# Pulsar_Buddy_rev_A.net
KiCad netlist of a schematic drawn in EAGLE
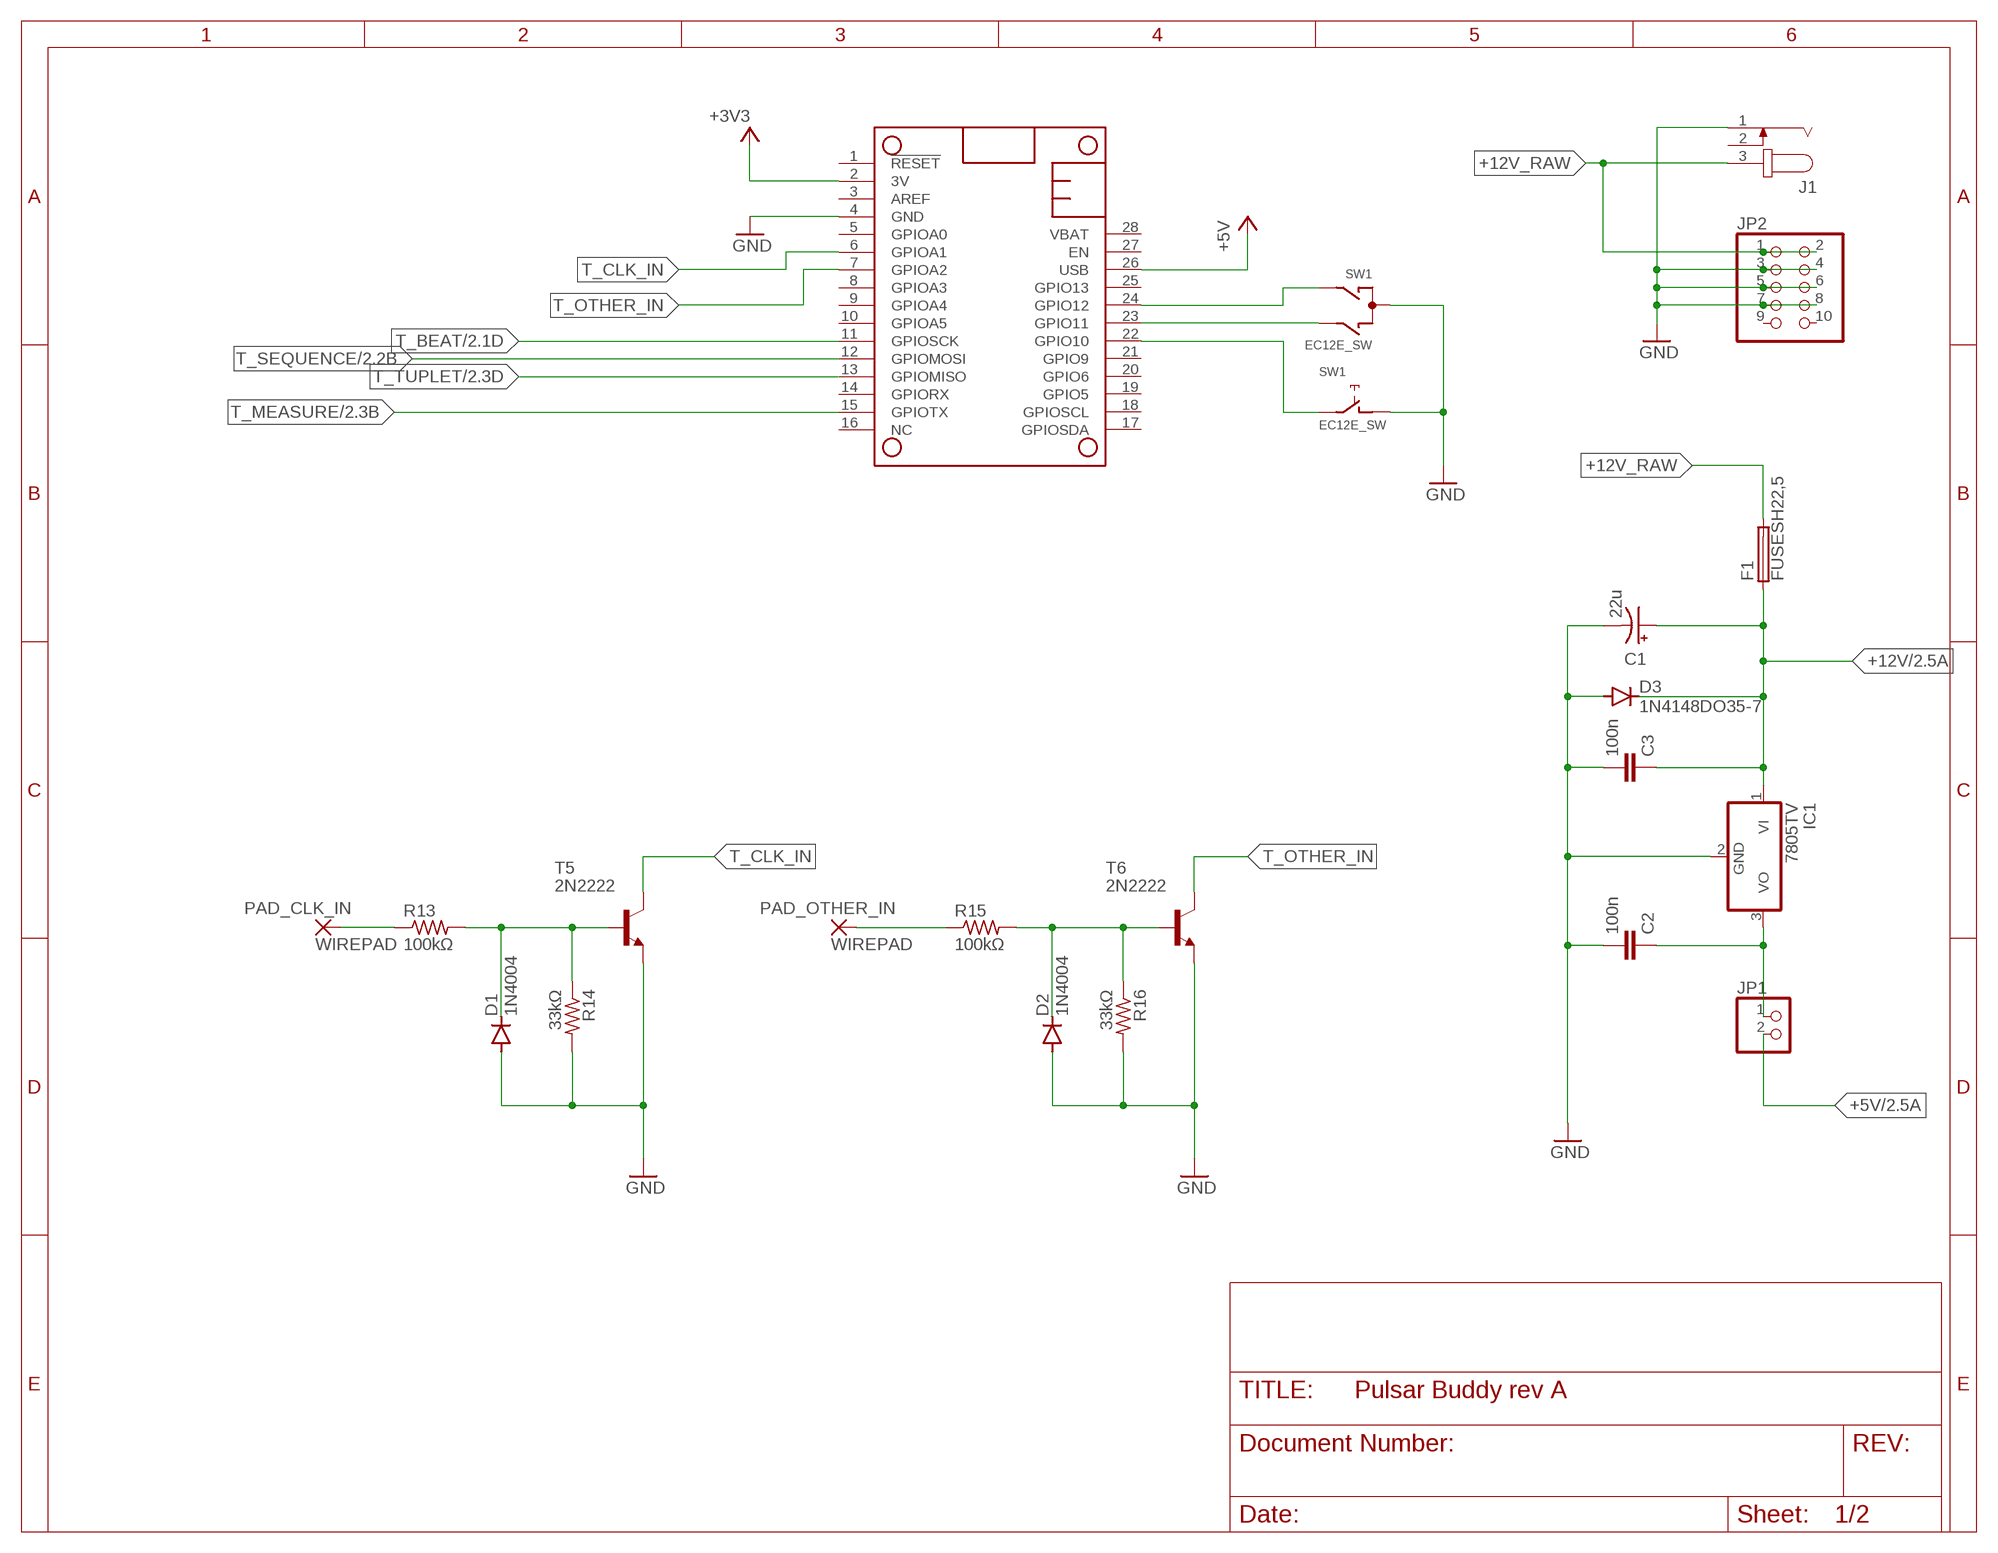
[diagram p0: schematic, sheet 1]
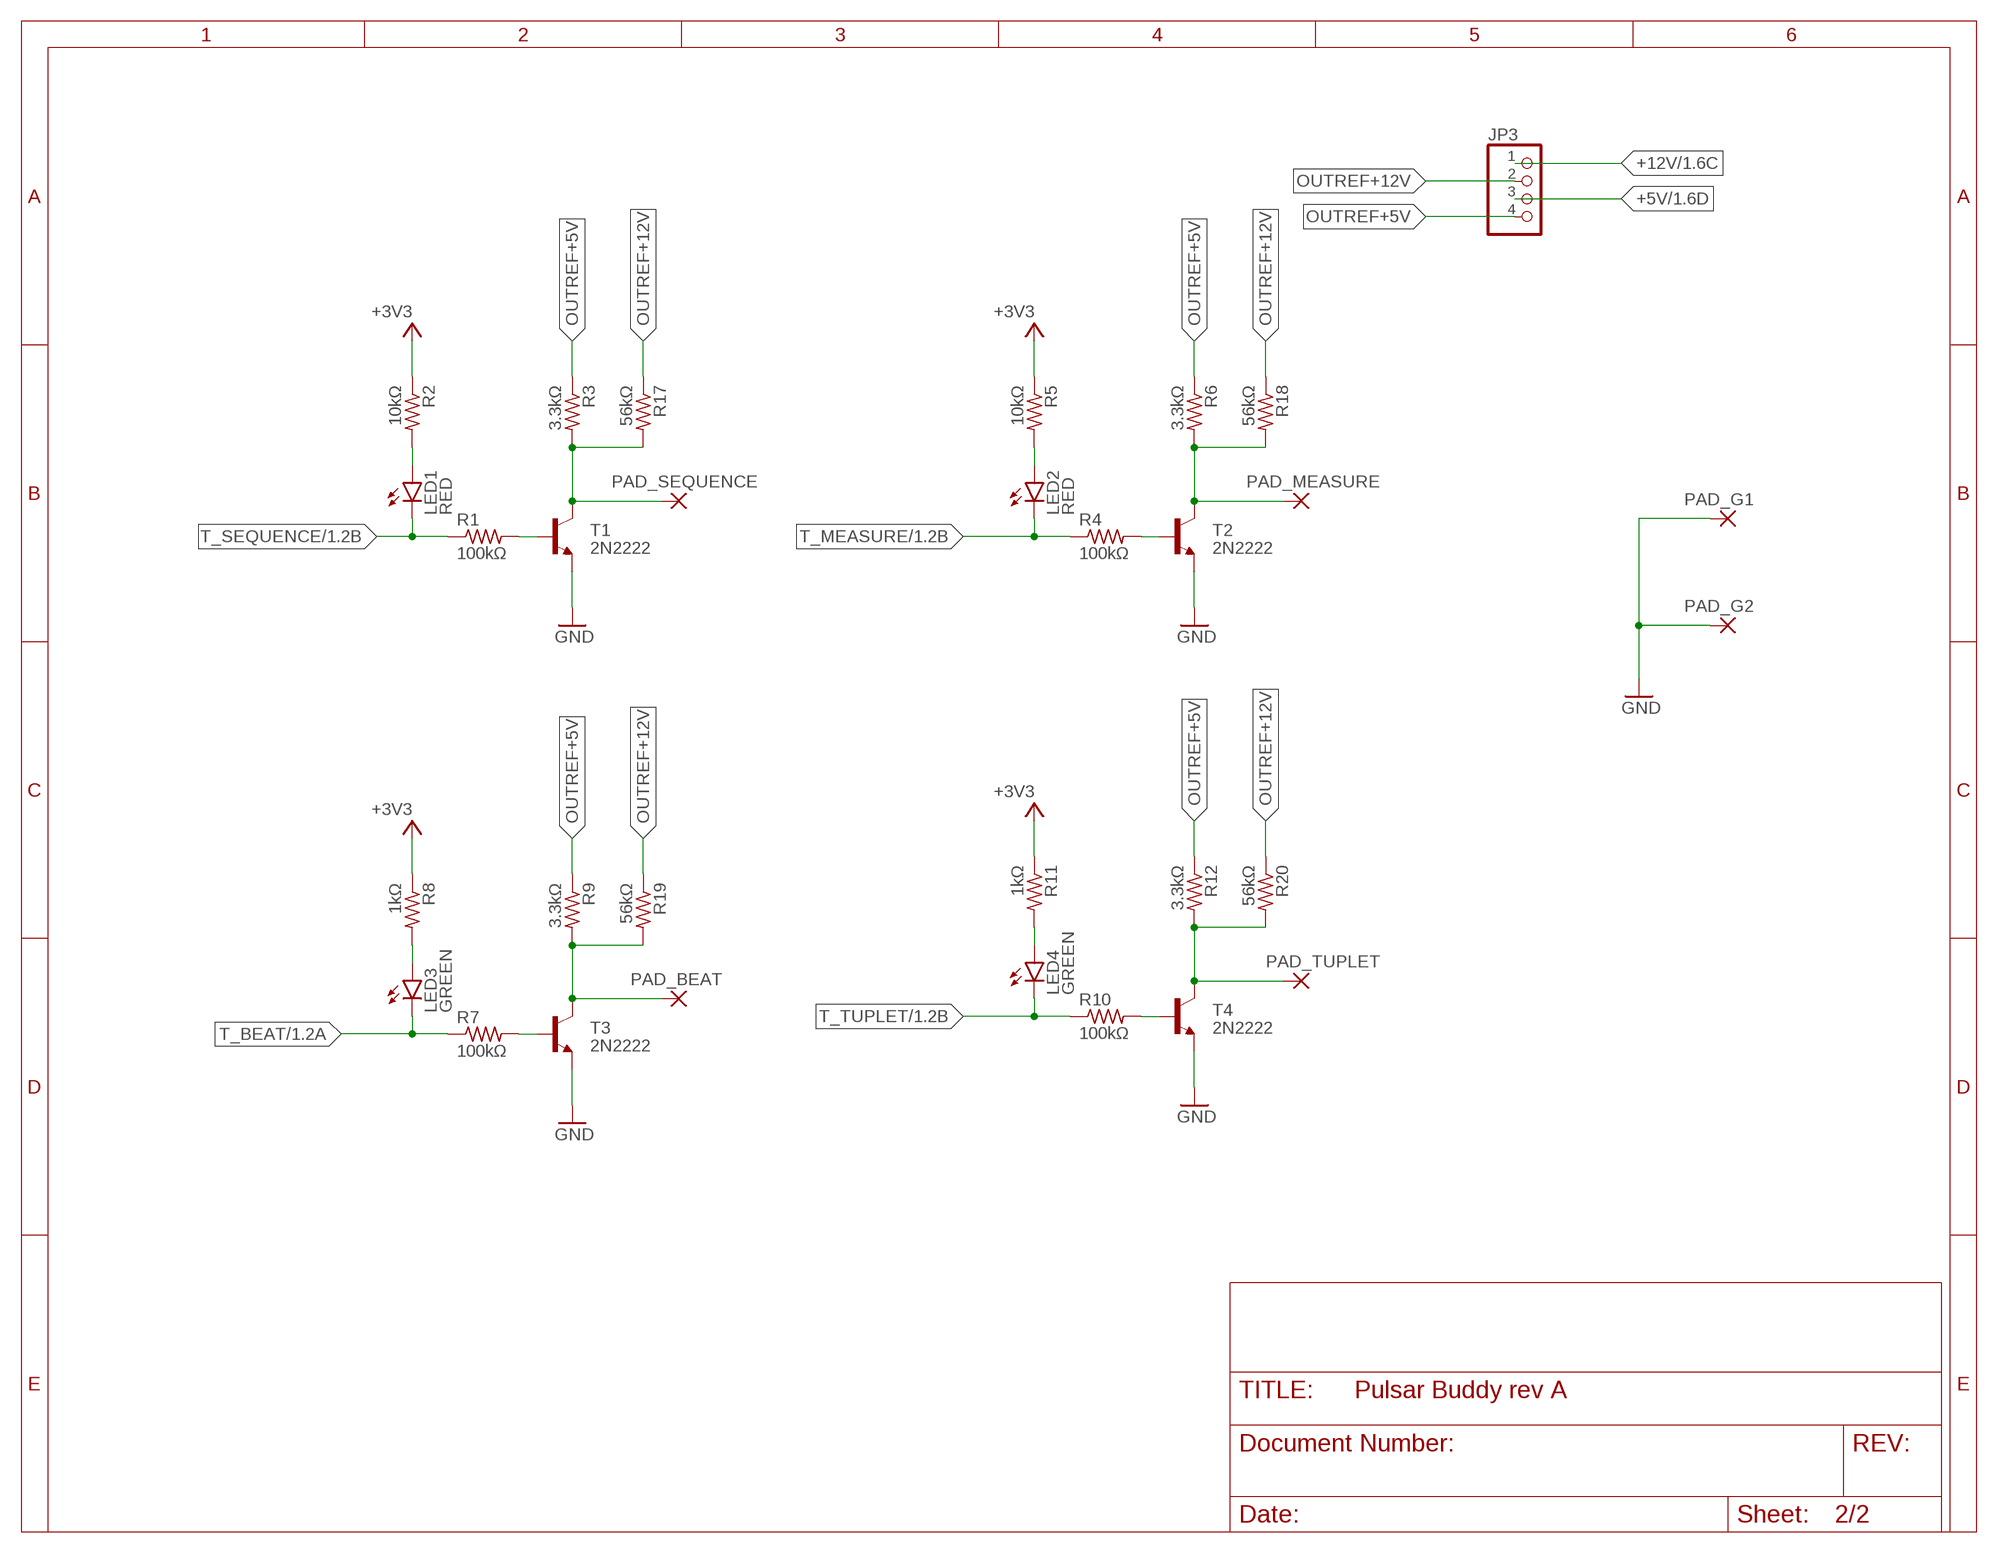
[diagram p1: schematic, sheet 2]

(export (version "E")
  (design (tool "Eeschema 10.0.6"))
  (components
    (comp (ref "C1")
      (value "22u")
      (footprint "eagle-import:E3,5-8")
      (libsource (lib "eagle-import") (part "CPOL-USE3.5-8"))
    )
    (comp (ref "C2")
      (value "100n")
      (footprint "eagle-import:C025-024X044")
      (libsource (lib "eagle-import") (part "C-EU025-024X044"))
    )
    (comp (ref "C3")
      (value "100n")
      (footprint "eagle-import:C025-024X044")
      (libsource (lib "eagle-import") (part "C-EU025-024X044"))
    )
    (comp (ref "D1")
      (value "1N4004")
      (footprint "eagle-import:DO41-10")
      (libsource (lib "eagle-import") (part "1N4004"))
    )
    (comp (ref "D2")
      (value "1N4004")
      (footprint "eagle-import:DO41-10")
      (libsource (lib "eagle-import") (part "1N4004"))
    )
    (comp (ref "D3")
      (value "1N4148DO35-7")
      (footprint "eagle-import:DO35-7")
      (libsource (lib "eagle-import") (part "1N4148DO35-7"))
    )
    (comp (ref "F1")
      (value "FUSESH22,5")
      (footprint "eagle-import:SH22,5")
      (libsource (lib "eagle-import") (part "FUSESH22,5"))
    )
    (comp (ref "IC1")
      (value "7805TV")
      (footprint "eagle-import:TO220V")
      (libsource (lib "eagle-import") (part "78TV05"))
    )
    (comp (ref "J1")
      (value "JACK-PLUG0")
      (footprint "eagle-import:SPC4077")
      (libsource (lib "eagle-import") (part "JACK-PLUG0"))
    )
    (comp (ref "JP1")
      (value "PINHD-1X2")
      (footprint "eagle-import:1X02")
      (libsource (lib "eagle-import") (part "PINHD-1X2"))
    )
    (comp (ref "JP2")
      (value "PINHD-2X5")
      (footprint "eagle-import:2X05")
      (libsource (lib "eagle-import") (part "PINHD-2X5"))
    )
    (comp (ref "MS2")
      (value "FEATHERWING_NODIM")
      (footprint "eagle-import:FEATHERWING_DIM")
      (libsource (lib "eagle-import") (part "FEATHERWING_NODIM"))
    )
    (comp (ref "PAD_CLK_IN")
      (value "WIREPAD")
      (footprint "eagle-import:M3")
      (libsource (lib "eagle-import") (part "WIREPAD"))
    )
    (comp (ref "PAD_OTHER_IN")
      (value "WIREPAD")
      (footprint "eagle-import:M3")
      (libsource (lib "eagle-import") (part "WIREPAD"))
    )
    (comp (ref "R13")
      (value "100kΩ")
      (footprint "eagle-import:0204_7")
      (libsource (lib "eagle-import") (part "R-US_0204/7"))
    )
    (comp (ref "R14")
      (value "33kΩ")
      (footprint "eagle-import:0204_7")
      (libsource (lib "eagle-import") (part "R-US_0204/7"))
    )
    (comp (ref "R15")
      (value "100kΩ")
      (footprint "eagle-import:0204_7")
      (libsource (lib "eagle-import") (part "R-US_0204/7"))
    )
    (comp (ref "R16")
      (value "33kΩ")
      (footprint "eagle-import:0204_7")
      (libsource (lib "eagle-import") (part "R-US_0204/7"))
    )
    (comp (ref "SW1")
      (value "EC12E_SW")
      (footprint "eagle-import:ALPS_EC12E_SW")
      (fields (field (name "MPN") "EC12E2424407"))
      (libsource (lib "eagle-import") (part "EC12E_SW"))
    )
    (comp (ref "T5")
      (value "2N2222")
      (footprint "eagle-import:TO92-EBC-OVAL")
      (libsource (lib "eagle-import") (part "2N2222"))
    )
    (comp (ref "T6")
      (value "2N2222")
      (footprint "eagle-import:TO92-EBC-OVAL")
      (libsource (lib "eagle-import") (part "2N2222"))
    )
    (comp (ref "JP3")
      (value "PINHD-1X4")
      (footprint "eagle-import:1X04")
      (libsource (lib "eagle-import") (part "PINHD-1X4"))
    )
    (comp (ref "LED1")
      (value "RED")
      (footprint "eagle-import:LED5MM")
      (libsource (lib "eagle-import") (part "LED5MM"))
    )
    (comp (ref "LED2")
      (value "RED")
      (footprint "eagle-import:LED5MM")
      (libsource (lib "eagle-import") (part "LED5MM"))
    )
    (comp (ref "LED3")
      (value "GREEN")
      (footprint "eagle-import:LED5MM")
      (libsource (lib "eagle-import") (part "LED5MM"))
    )
    (comp (ref "LED4")
      (value "GREEN")
      (footprint "eagle-import:LED5MM")
      (libsource (lib "eagle-import") (part "LED5MM"))
    )
    (comp (ref "PAD_BEAT")
      (value "WIREPAD")
      (footprint "eagle-import:M3")
      (libsource (lib "eagle-import") (part "WIREPAD"))
    )
    (comp (ref "PAD_G1")
      (value "WIREPAD")
      (footprint "eagle-import:M3")
      (libsource (lib "eagle-import") (part "WIREPAD"))
    )
    (comp (ref "PAD_G2")
      (value "WIREPAD")
      (footprint "eagle-import:M3")
      (libsource (lib "eagle-import") (part "WIREPAD"))
    )
    (comp (ref "PAD_MEASURE")
      (value "WIREPAD")
      (footprint "eagle-import:M3")
      (libsource (lib "eagle-import") (part "WIREPAD"))
    )
    (comp (ref "PAD_SEQUENCE")
      (value "WIREPAD")
      (footprint "eagle-import:M3")
      (libsource (lib "eagle-import") (part "WIREPAD"))
    )
    (comp (ref "PAD_TUPLET")
      (value "WIREPAD")
      (footprint "eagle-import:M3")
      (libsource (lib "eagle-import") (part "WIREPAD"))
    )
    (comp (ref "R1")
      (value "100kΩ")
      (footprint "eagle-import:0204_7")
      (libsource (lib "eagle-import") (part "R-US_0204/7"))
    )
    (comp (ref "R2")
      (value "10kΩ")
      (footprint "eagle-import:0204_7")
      (libsource (lib "eagle-import") (part "R-US_0204/7"))
    )
    (comp (ref "R3")
      (value "3.3kΩ")
      (footprint "eagle-import:0204_7")
      (libsource (lib "eagle-import") (part "R-US_0204/7"))
    )
    (comp (ref "R4")
      (value "100kΩ")
      (footprint "eagle-import:0204_7")
      (libsource (lib "eagle-import") (part "R-US_0204/7"))
    )
    (comp (ref "R5")
      (value "10kΩ")
      (footprint "eagle-import:0204_7")
      (libsource (lib "eagle-import") (part "R-US_0204/7"))
    )
    (comp (ref "R6")
      (value "3.3kΩ")
      (footprint "eagle-import:0204_7")
      (libsource (lib "eagle-import") (part "R-US_0204/7"))
    )
    (comp (ref "R7")
      (value "100kΩ")
      (footprint "eagle-import:0204_7")
      (libsource (lib "eagle-import") (part "R-US_0204/7"))
    )
    (comp (ref "R8")
      (value "1kΩ")
      (footprint "eagle-import:0204_7")
      (libsource (lib "eagle-import") (part "R-US_0204/7"))
    )
    (comp (ref "R9")
      (value "3.3kΩ")
      (footprint "eagle-import:0204_7")
      (libsource (lib "eagle-import") (part "R-US_0204/7"))
    )
    (comp (ref "R10")
      (value "100kΩ")
      (footprint "eagle-import:0204_7")
      (libsource (lib "eagle-import") (part "R-US_0204/7"))
    )
    (comp (ref "R11")
      (value "1kΩ")
      (footprint "eagle-import:0204_7")
      (libsource (lib "eagle-import") (part "R-US_0204/7"))
    )
    (comp (ref "R12")
      (value "3.3kΩ")
      (footprint "eagle-import:0204_7")
      (libsource (lib "eagle-import") (part "R-US_0204/7"))
    )
    (comp (ref "R17")
      (value "56kΩ")
      (footprint "eagle-import:0204_7")
      (libsource (lib "eagle-import") (part "R-US_0204/7"))
    )
    (comp (ref "R18")
      (value "56kΩ")
      (footprint "eagle-import:0204_7")
      (libsource (lib "eagle-import") (part "R-US_0204/7"))
    )
    (comp (ref "R19")
      (value "56kΩ")
      (footprint "eagle-import:0204_7")
      (libsource (lib "eagle-import") (part "R-US_0204/7"))
    )
    (comp (ref "R20")
      (value "56kΩ")
      (footprint "eagle-import:0204_7")
      (libsource (lib "eagle-import") (part "R-US_0204/7"))
    )
    (comp (ref "T1")
      (value "2N2222")
      (footprint "eagle-import:TO92-EBC-OVAL")
      (libsource (lib "eagle-import") (part "2N2222"))
    )
    (comp (ref "T2")
      (value "2N2222")
      (footprint "eagle-import:TO92-EBC-OVAL")
      (libsource (lib "eagle-import") (part "2N2222"))
    )
    (comp (ref "T3")
      (value "2N2222")
      (footprint "eagle-import:TO92-EBC-OVAL")
      (libsource (lib "eagle-import") (part "2N2222"))
    )
    (comp (ref "T4")
      (value "2N2222")
      (footprint "eagle-import:TO92-EBC-OVAL")
      (libsource (lib "eagle-import") (part "2N2222"))
    )
  )
  (nets
    (net (code "1") (name "+3V3") (class "Default")
      (node (ref "MS2") (pin "2") (pinfunction "3V_2") (pintype "power_in"))
      (node (ref "R11") (pin "1") (pinfunction "1_1") (pintype "passive"))
      (node (ref "R2") (pin "1") (pinfunction "1_1") (pintype "passive"))
      (node (ref "R5") (pin "1") (pinfunction "1_1") (pintype "passive"))
      (node (ref "R8") (pin "1") (pinfunction "1_1") (pintype "passive"))
    )
    (net (code "2") (name "+5V") (class "Default")
      (node (ref "JP1") (pin "2") (pinfunction "2_2") (pintype "passive"))
      (node (ref "JP3") (pin "3") (pinfunction "3_3") (pintype "passive"))
      (node (ref "MS2") (pin "26") (pinfunction "USB_26") (pintype "power_in"))
    )
    (net (code "3") (name "+12V") (class "Default")
      (node (ref "C1") (pin "+") (pinfunction "+_+") (pintype "passive"))
      (node (ref "C3") (pin "1") (pinfunction "1_1") (pintype "passive"))
      (node (ref "D3") (pin "C") (pinfunction "C_C") (pintype "passive"))
      (node (ref "F1") (pin "1") (pinfunction "1_1") (pintype "passive"))
      (node (ref "IC1") (pin "1") (pinfunction "VI_1") (pintype "input"))
      (node (ref "JP3") (pin "1") (pinfunction "1_1") (pintype "passive"))
    )
    (net (code "4") (name "+12V_RAW") (class "Default")
      (node (ref "F1") (pin "2") (pinfunction "2_2") (pintype "passive"))
      (node (ref "J1") (pin "3") (pinfunction "3_3") (pintype "passive"))
      (node (ref "JP2") (pin "1") (pinfunction "1_1") (pintype "passive"))
      (node (ref "JP2") (pin "2") (pinfunction "2_2") (pintype "passive"))
    )
    (net (code "5") (name "GND") (class "Default")
      (node (ref "C1") (pin "-") (pinfunction "-_-") (pintype "passive"))
      (node (ref "C2") (pin "2") (pinfunction "2_2") (pintype "passive"))
      (node (ref "C3") (pin "2") (pinfunction "2_2") (pintype "passive"))
      (node (ref "D1") (pin "A") (pinfunction "A_A") (pintype "passive"))
      (node (ref "D2") (pin "A") (pinfunction "A_A") (pintype "passive"))
      (node (ref "D3") (pin "A") (pinfunction "A_A") (pintype "passive"))
      (node (ref "IC1") (pin "2") (pinfunction "GND_2") (pintype "passive"))
      (node (ref "J1") (pin "1") (pinfunction "1_1") (pintype "passive"))
      (node (ref "JP2") (pin "3") (pinfunction "3_3") (pintype "passive"))
      (node (ref "JP2") (pin "4") (pinfunction "4_4") (pintype "passive"))
      (node (ref "JP2") (pin "5") (pinfunction "5_5") (pintype "passive"))
      (node (ref "JP2") (pin "6") (pinfunction "6_6") (pintype "passive"))
      (node (ref "JP2") (pin "7") (pinfunction "7_7") (pintype "passive"))
      (node (ref "JP2") (pin "8") (pinfunction "8_8") (pintype "passive"))
      (node (ref "MS2") (pin "4") (pinfunction "GND_4") (pintype "power_in"))
      (node (ref "PAD_G1") (pin "1") (pinfunction "P_1") (pintype "passive"))
      (node (ref "PAD_G2") (pin "1") (pinfunction "P_1") (pintype "passive"))
      (node (ref "R14") (pin "2") (pinfunction "2_2") (pintype "passive"))
      (node (ref "R16") (pin "2") (pinfunction "2_2") (pintype "passive"))
      (node (ref "SW1") (pin "C") (pinfunction "C_C") (pintype "passive"))
      (node (ref "SW1") (pin "D") (pinfunction "1_D") (pintype "passive"))
      (node (ref "T1") (pin "E") (pinfunction "E_E") (pintype "passive"))
      (node (ref "T2") (pin "E") (pinfunction "E_E") (pintype "passive"))
      (node (ref "T3") (pin "E") (pinfunction "E_E") (pintype "passive"))
      (node (ref "T4") (pin "E") (pinfunction "E_E") (pintype "passive"))
      (node (ref "T5") (pin "E") (pinfunction "E_E") (pintype "passive"))
      (node (ref "T6") (pin "E") (pinfunction "E_E") (pintype "passive"))
    )
    (net (code "6") (name "Net-(D1-PadC)") (class "Default")
      (node (ref "D1") (pin "C") (pinfunction "C_C") (pintype "passive"))
      (node (ref "R13") (pin "2") (pinfunction "2_2") (pintype "passive"))
      (node (ref "R14") (pin "1") (pinfunction "1_1") (pintype "passive"))
      (node (ref "T5") (pin "B") (pinfunction "B_B") (pintype "passive"))
    )
    (net (code "7") (name "Net-(D2-PadC)") (class "Default")
      (node (ref "D2") (pin "C") (pinfunction "C_C") (pintype "passive"))
      (node (ref "R15") (pin "2") (pinfunction "2_2") (pintype "passive"))
      (node (ref "R16") (pin "1") (pinfunction "1_1") (pintype "passive"))
      (node (ref "T6") (pin "B") (pinfunction "B_B") (pintype "passive"))
    )
    (net (code "8") (name "Net-(IC1-VO)") (class "Default")
      (node (ref "C2") (pin "1") (pinfunction "1_1") (pintype "passive"))
      (node (ref "IC1") (pin "3") (pinfunction "VO_3") (pintype "passive"))
      (node (ref "JP1") (pin "1") (pinfunction "1_1") (pintype "passive"))
    )
    (net (code "9") (name "Net-(LED1-PadA)") (class "Default")
      (node (ref "LED1") (pin "A") (pinfunction "A_A") (pintype "passive"))
      (node (ref "R2") (pin "2") (pinfunction "2_2") (pintype "passive"))
    )
    (net (code "10") (name "Net-(LED2-PadA)") (class "Default")
      (node (ref "LED2") (pin "A") (pinfunction "A_A") (pintype "passive"))
      (node (ref "R5") (pin "2") (pinfunction "2_2") (pintype "passive"))
    )
    (net (code "11") (name "Net-(LED3-PadA)") (class "Default")
      (node (ref "LED3") (pin "A") (pinfunction "A_A") (pintype "passive"))
      (node (ref "R8") (pin "2") (pinfunction "2_2") (pintype "passive"))
    )
    (net (code "12") (name "Net-(LED4-PadA)") (class "Default")
      (node (ref "LED4") (pin "A") (pinfunction "A_A") (pintype "passive"))
      (node (ref "R11") (pin "2") (pinfunction "2_2") (pintype "passive"))
    )
    (net (code "13") (name "Net-(MS2-GPIO10)") (class "Default")
      (node (ref "MS2") (pin "22") (pinfunction "GPIO10_22") (pintype "bidirectional"))
      (node (ref "SW1") (pin "E") (pinfunction "2_E") (pintype "passive"))
    )
    (net (code "14") (name "Net-(MS2-GPIO11)") (class "Default")
      (node (ref "MS2") (pin "23") (pinfunction "GPIO11_23") (pintype "bidirectional"))
      (node (ref "SW1") (pin "B") (pinfunction "B_B") (pintype "passive"))
    )
    (net (code "15") (name "Net-(MS2-GPIO12)") (class "Default")
      (node (ref "MS2") (pin "24") (pinfunction "GPIO12_24") (pintype "bidirectional"))
      (node (ref "SW1") (pin "A") (pinfunction "A_A") (pintype "passive"))
    )
    (net (code "16") (name "Net-(PAD_BEAT-P)") (class "Default")
      (node (ref "PAD_BEAT") (pin "1") (pinfunction "P_1") (pintype "passive"))
      (node (ref "R19") (pin "2") (pinfunction "2_2") (pintype "passive"))
      (node (ref "R9") (pin "2") (pinfunction "2_2") (pintype "passive"))
      (node (ref "T3") (pin "C") (pinfunction "C_C") (pintype "passive"))
    )
    (net (code "17") (name "Net-(PAD_CLK_IN-P)") (class "Default")
      (node (ref "PAD_CLK_IN") (pin "1") (pinfunction "P_1") (pintype "passive"))
      (node (ref "R13") (pin "1") (pinfunction "1_1") (pintype "passive"))
    )
    (net (code "18") (name "Net-(PAD_MEASURE-P)") (class "Default")
      (node (ref "PAD_MEASURE") (pin "1") (pinfunction "P_1") (pintype "passive"))
      (node (ref "R18") (pin "2") (pinfunction "2_2") (pintype "passive"))
      (node (ref "R6") (pin "2") (pinfunction "2_2") (pintype "passive"))
      (node (ref "T2") (pin "C") (pinfunction "C_C") (pintype "passive"))
    )
    (net (code "19") (name "Net-(PAD_OTHER_IN-P)") (class "Default")
      (node (ref "PAD_OTHER_IN") (pin "1") (pinfunction "P_1") (pintype "passive"))
      (node (ref "R15") (pin "1") (pinfunction "1_1") (pintype "passive"))
    )
    (net (code "20") (name "Net-(PAD_SEQUENCE-P)") (class "Default")
      (node (ref "PAD_SEQUENCE") (pin "1") (pinfunction "P_1") (pintype "passive"))
      (node (ref "R17") (pin "2") (pinfunction "2_2") (pintype "passive"))
      (node (ref "R3") (pin "2") (pinfunction "2_2") (pintype "passive"))
      (node (ref "T1") (pin "C") (pinfunction "C_C") (pintype "passive"))
    )
    (net (code "21") (name "Net-(PAD_TUPLET-P)") (class "Default")
      (node (ref "PAD_TUPLET") (pin "1") (pinfunction "P_1") (pintype "passive"))
      (node (ref "R12") (pin "2") (pinfunction "2_2") (pintype "passive"))
      (node (ref "R20") (pin "2") (pinfunction "2_2") (pintype "passive"))
      (node (ref "T4") (pin "C") (pinfunction "C_C") (pintype "passive"))
    )
    (net (code "22") (name "Net-(R1-Pad2)") (class "Default")
      (node (ref "R1") (pin "2") (pinfunction "2_2") (pintype "passive"))
      (node (ref "T1") (pin "B") (pinfunction "B_B") (pintype "passive"))
    )
    (net (code "23") (name "Net-(R4-Pad2)") (class "Default")
      (node (ref "R4") (pin "2") (pinfunction "2_2") (pintype "passive"))
      (node (ref "T2") (pin "B") (pinfunction "B_B") (pintype "passive"))
    )
    (net (code "24") (name "Net-(R7-Pad2)") (class "Default")
      (node (ref "R7") (pin "2") (pinfunction "2_2") (pintype "passive"))
      (node (ref "T3") (pin "B") (pinfunction "B_B") (pintype "passive"))
    )
    (net (code "25") (name "Net-(R10-Pad2)") (class "Default")
      (node (ref "R10") (pin "2") (pinfunction "2_2") (pintype "passive"))
      (node (ref "T4") (pin "B") (pinfunction "B_B") (pintype "passive"))
    )
    (net (code "26") (name "OUTREF+5V") (class "Default")
      (node (ref "JP3") (pin "4") (pinfunction "4_4") (pintype "passive"))
      (node (ref "R12") (pin "1") (pinfunction "1_1") (pintype "passive"))
      (node (ref "R3") (pin "1") (pinfunction "1_1") (pintype "passive"))
      (node (ref "R6") (pin "1") (pinfunction "1_1") (pintype "passive"))
      (node (ref "R9") (pin "1") (pinfunction "1_1") (pintype "passive"))
    )
    (net (code "27") (name "OUTREF+12V") (class "Default")
      (node (ref "JP3") (pin "2") (pinfunction "2_2") (pintype "passive"))
      (node (ref "R17") (pin "1") (pinfunction "1_1") (pintype "passive"))
      (node (ref "R18") (pin "1") (pinfunction "1_1") (pintype "passive"))
      (node (ref "R19") (pin "1") (pinfunction "1_1") (pintype "passive"))
      (node (ref "R20") (pin "1") (pinfunction "1_1") (pintype "passive"))
    )
    (net (code "28") (name "T_BEAT") (class "Default")
      (node (ref "LED3") (pin "K") (pinfunction "C_K") (pintype "passive"))
      (node (ref "MS2") (pin "11") (pinfunction "GPIOSCK_11") (pintype "bidirectional"))
      (node (ref "R7") (pin "1") (pinfunction "1_1") (pintype "passive"))
    )
    (net (code "29") (name "T_CLK_IN") (class "Default")
      (node (ref "MS2") (pin "6") (pinfunction "GPIOA1_6") (pintype "bidirectional"))
      (node (ref "T5") (pin "C") (pinfunction "C_C") (pintype "passive"))
    )
    (net (code "30") (name "T_MEASURE") (class "Default")
      (node (ref "LED2") (pin "K") (pinfunction "C_K") (pintype "passive"))
      (node (ref "MS2") (pin "15") (pinfunction "GPIOTX_15") (pintype "bidirectional"))
      (node (ref "R4") (pin "1") (pinfunction "1_1") (pintype "passive"))
    )
    (net (code "31") (name "T_OTHER_IN") (class "Default")
      (node (ref "MS2") (pin "7") (pinfunction "GPIOA2_7") (pintype "bidirectional"))
      (node (ref "T6") (pin "C") (pinfunction "C_C") (pintype "passive"))
    )
    (net (code "32") (name "T_SEQUENCE") (class "Default")
      (node (ref "LED1") (pin "K") (pinfunction "C_K") (pintype "passive"))
      (node (ref "MS2") (pin "12") (pinfunction "GPIOMOSI_12") (pintype "bidirectional"))
      (node (ref "R1") (pin "1") (pinfunction "1_1") (pintype "passive"))
    )
    (net (code "33") (name "T_TUPLET") (class "Default")
      (node (ref "LED4") (pin "K") (pinfunction "C_K") (pintype "passive"))
      (node (ref "MS2") (pin "13") (pinfunction "GPIOMISO_13") (pintype "bidirectional"))
      (node (ref "R10") (pin "1") (pinfunction "1_1") (pintype "passive"))
    )
    (net (code "34") (name "VBAT") (class "Default")
      (node (ref "MS2") (pin "28") (pinfunction "VBAT_28") (pintype "power_in"))
    )
    (net (code "35") (name "unconnected-(J1-Pad2)") (class "Default")
      (node (ref "J1") (pin "2") (pinfunction "2_2") (pintype "passive"))
    )
    (net (code "36") (name "unconnected-(JP2-Pad9)") (class "Default")
      (node (ref "JP2") (pin "9") (pinfunction "9_9") (pintype "passive"))
    )
    (net (code "37") (name "unconnected-(JP2-Pad10)") (class "Default")
      (node (ref "JP2") (pin "10") (pinfunction "10_10") (pintype "passive"))
    )
    (net (code "38") (name "unconnected-(MS2-AREF-Pad3)") (class "Default")
      (node (ref "MS2") (pin "3") (pinfunction "AREF_3") (pintype "passive"))
    )
    (net (code "39") (name "unconnected-(MS2-EN-Pad27)") (class "Default")
      (node (ref "MS2") (pin "27") (pinfunction "EN_27") (pintype "passive"))
    )
    (net (code "40") (name "unconnected-(MS2-GPIO5-Pad19)") (class "Default")
      (node (ref "MS2") (pin "19") (pinfunction "GPIO5_19") (pintype "bidirectional"))
    )
    (net (code "41") (name "unconnected-(MS2-GPIO6-Pad20)") (class "Default")
      (node (ref "MS2") (pin "20") (pinfunction "GPIO6_20") (pintype "bidirectional"))
    )
    (net (code "42") (name "unconnected-(MS2-GPIO9-Pad21)") (class "Default")
      (node (ref "MS2") (pin "21") (pinfunction "GPIO9_21") (pintype "bidirectional"))
    )
    (net (code "43") (name "unconnected-(MS2-GPIO13-Pad25)") (class "Default")
      (node (ref "MS2") (pin "25") (pinfunction "GPIO13_25") (pintype "bidirectional"))
    )
    (net (code "44") (name "unconnected-(MS2-GPIOA0-Pad5)") (class "Default")
      (node (ref "MS2") (pin "5") (pinfunction "GPIOA0_5") (pintype "bidirectional"))
    )
    (net (code "45") (name "unconnected-(MS2-GPIOA3-Pad8)") (class "Default")
      (node (ref "MS2") (pin "8") (pinfunction "GPIOA3_8") (pintype "bidirectional"))
    )
    (net (code "46") (name "unconnected-(MS2-GPIOA4-Pad9)") (class "Default")
      (node (ref "MS2") (pin "9") (pinfunction "GPIOA4_9") (pintype "bidirectional"))
    )
    (net (code "47") (name "unconnected-(MS2-GPIOA5-Pad10)") (class "Default")
      (node (ref "MS2") (pin "10") (pinfunction "GPIOA5_10") (pintype "bidirectional"))
    )
    (net (code "48") (name "unconnected-(MS2-GPIORX-Pad14)") (class "Default")
      (node (ref "MS2") (pin "14") (pinfunction "GPIORX_14") (pintype "bidirectional"))
    )
    (net (code "49") (name "unconnected-(MS2-GPIOSCL-Pad18)") (class "Default")
      (node (ref "MS2") (pin "18") (pinfunction "GPIOSCL_18") (pintype "bidirectional"))
    )
    (net (code "50") (name "unconnected-(MS2-GPIOSDA-Pad17)") (class "Default")
      (node (ref "MS2") (pin "17") (pinfunction "GPIOSDA_17") (pintype "bidirectional"))
    )
    (net (code "51") (name "unconnected-(MS2-NC-Pad16)") (class "Default")
      (node (ref "MS2") (pin "16") (pinfunction "NC_16") (pintype "passive"))
    )
    (net (code "52") (name "unconnected-(MS2-~{RESET}-Pad1)") (class "Default")
      (node (ref "MS2") (pin "1") (pinfunction "~{RESET}_1") (pintype "input"))
    )
  )
)
